# 1-Schematic_ACS2STM-alternate-IDC.net
KiCad netlist of a schematic drawn in EasyEDA
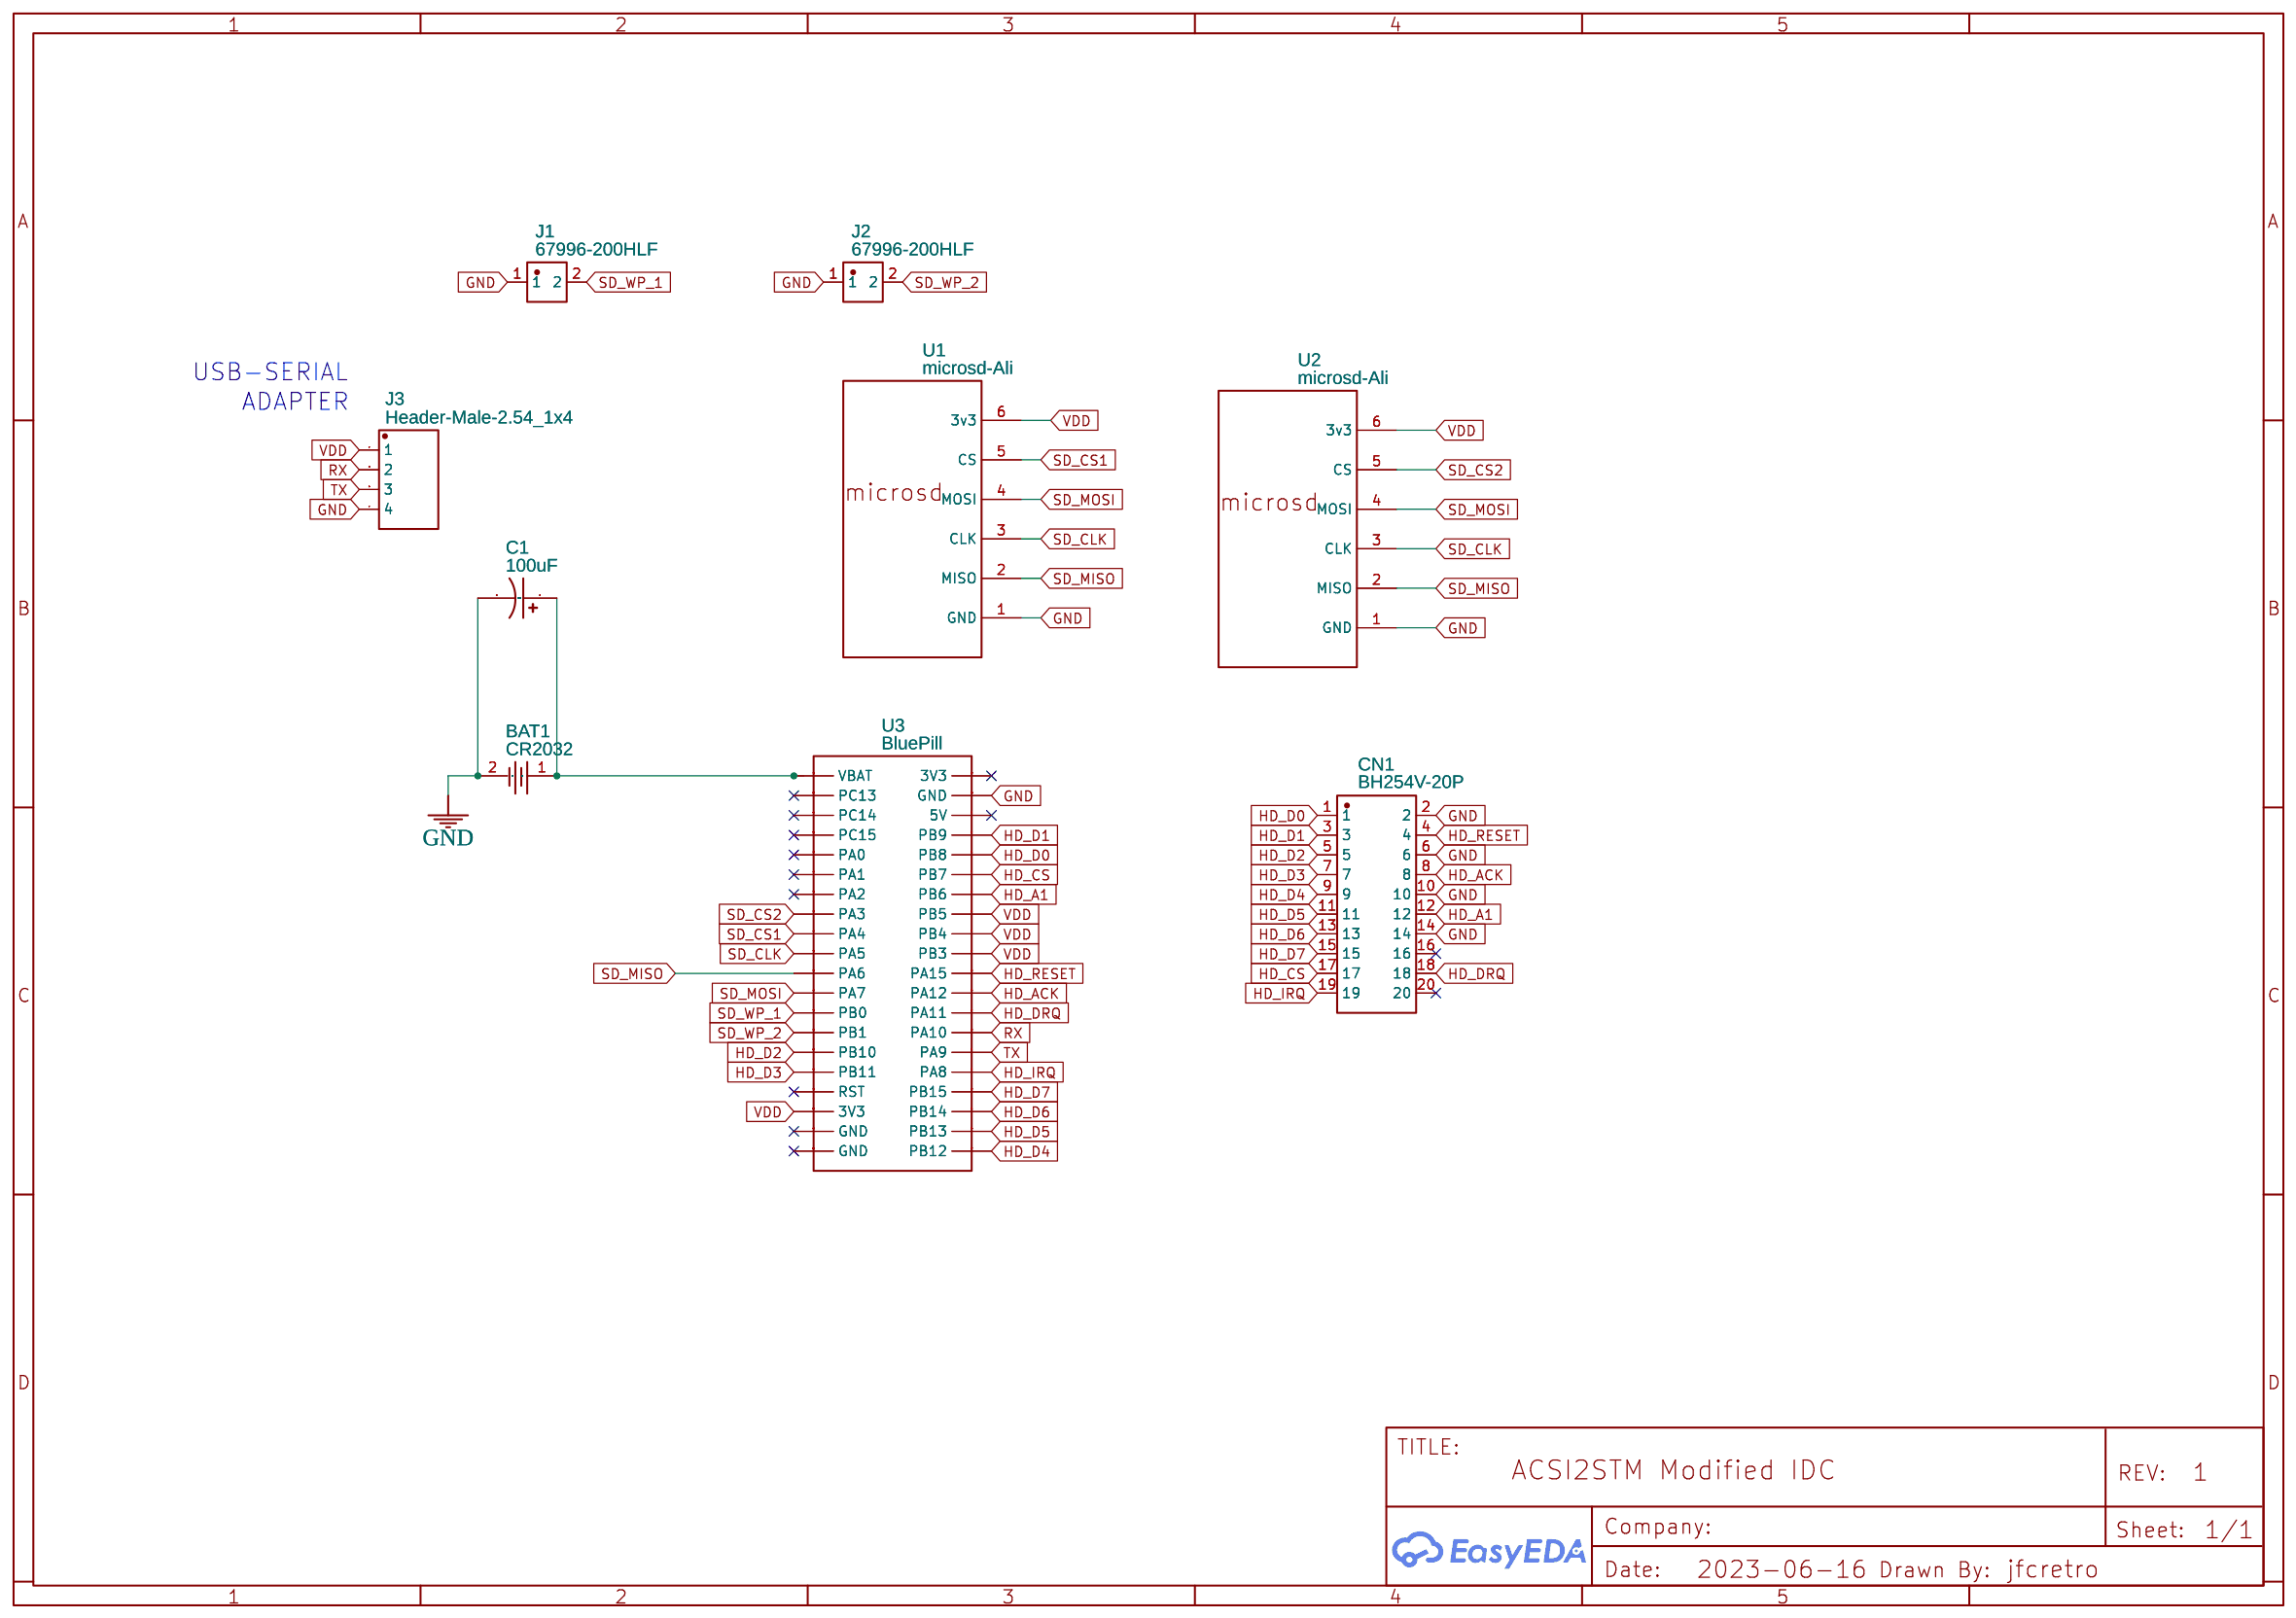
[diagram p0: schematic sheet]

(export (version "E")
  (design (tool "Eeschema 10.0.6"))
  (components
    (comp (ref "BAT1")
      (value "CR2032")
      (fields (field (name "BOM_Supplier Part") "C9900007674"))
      (libsource (lib "") (part "CR2032_C9900007674"))
    )
    (comp (ref "C1") (value "100uF") (libsource (lib "") (part "CE_TH_D6.3×F2.5_US")))
    (comp (ref "CN1")
      (value "BH254V-20P")
      (fields (field (name "BOM_Supplier Part") "C492444"))
      (libsource (lib "") (part "BH254V-20P"))
    )
    (comp (ref "J1")
      (value "67996-200HLF")
      (fields (field (name "BOM_Supplier Part") "C236045"))
      (libsource (lib "") (part "67996-200HLF"))
    )
    (comp (ref "J2")
      (value "67996-200HLF")
      (fields (field (name "BOM_Supplier Part") "C236045"))
      (libsource (lib "") (part "67996-200HLF"))
    )
    (comp (ref "J3")
      (value "Header-Male-2.54_1x4")
      (fields
        (field (name "BOM_Manufacturer Part") "B-2100S04P-A110")
        (field (name "BOM_Supplier Part") "C124378")
      )
      (libsource (lib "") (part "Header-Male-2.54_1x4"))
    )
    (comp (ref "U1") (value "microsd-Ali") (libsource (lib "") (part "microsd-Ali")))
    (comp (ref "U2") (value "microsd-Ali") (libsource (lib "") (part "microsd-Ali")))
    (comp (ref "U3") (value "BluePill") (libsource (lib "") (part "BluePill")))
  )
  (nets
    (net (code "1") (name "GND") (class "Default")
      (node (ref "BAT1") (pin "2") (pinfunction "2_2") (pintype "input"))
      (node (ref "C1") (pin "2") (pinfunction "2_2") (pintype "unspecified"))
      (node (ref "CN1") (pin "10") (pinfunction "10_10") (pintype "unspecified"))
      (node (ref "CN1") (pin "14") (pinfunction "14_14") (pintype "unspecified"))
      (node (ref "CN1") (pin "2") (pinfunction "2_2") (pintype "unspecified"))
      (node (ref "CN1") (pin "6") (pinfunction "6_6") (pintype "unspecified"))
      (node (ref "J1") (pin "1") (pinfunction "1_1") (pintype "unspecified"))
      (node (ref "J2") (pin "1") (pinfunction "1_1") (pintype "unspecified"))
      (node (ref "J3") (pin "4") (pinfunction "4_4") (pintype "unspecified"))
      (node (ref "U1") (pin "1") (pinfunction "GND_1") (pintype "unspecified"))
      (node (ref "U2") (pin "1") (pinfunction "GND_1") (pintype "unspecified"))
      (node (ref "U3") (pin "GND_3") (pinfunction "GND_GND_3") (pintype "unspecified"))
    )
    (net (code "2") (name "HD_A1") (class "Default")
      (node (ref "CN1") (pin "12") (pinfunction "12_12") (pintype "unspecified"))
      (node (ref "U3") (pin "PB6") (pinfunction "PB6_PB6") (pintype "unspecified"))
    )
    (net (code "3") (name "HD_ACK") (class "Default")
      (node (ref "CN1") (pin "8") (pinfunction "8_8") (pintype "unspecified"))
      (node (ref "U3") (pin "PA12") (pinfunction "PA12_PA12") (pintype "unspecified"))
    )
    (net (code "4") (name "HD_CS") (class "Default")
      (node (ref "CN1") (pin "17") (pinfunction "17_17") (pintype "unspecified"))
      (node (ref "U3") (pin "PB7") (pinfunction "PB7_PB7") (pintype "unspecified"))
    )
    (net (code "5") (name "HD_D0") (class "Default")
      (node (ref "CN1") (pin "1") (pinfunction "1_1") (pintype "unspecified"))
      (node (ref "U3") (pin "PB8") (pinfunction "PB8_PB8") (pintype "unspecified"))
    )
    (net (code "6") (name "HD_D1") (class "Default")
      (node (ref "CN1") (pin "3") (pinfunction "3_3") (pintype "unspecified"))
      (node (ref "U3") (pin "PB9") (pinfunction "PB9_PB9") (pintype "unspecified"))
    )
    (net (code "7") (name "HD_D2") (class "Default")
      (node (ref "CN1") (pin "5") (pinfunction "5_5") (pintype "unspecified"))
      (node (ref "U3") (pin "PB10") (pinfunction "PB10_PB10") (pintype "unspecified"))
    )
    (net (code "8") (name "HD_D3") (class "Default")
      (node (ref "CN1") (pin "7") (pinfunction "7_7") (pintype "unspecified"))
      (node (ref "U3") (pin "PB11") (pinfunction "PB11_PB11") (pintype "unspecified"))
    )
    (net (code "9") (name "HD_D4") (class "Default")
      (node (ref "CN1") (pin "9") (pinfunction "9_9") (pintype "unspecified"))
      (node (ref "U3") (pin "PB12") (pinfunction "PB12_PB12") (pintype "unspecified"))
    )
    (net (code "10") (name "HD_D5") (class "Default")
      (node (ref "CN1") (pin "11") (pinfunction "11_11") (pintype "unspecified"))
      (node (ref "U3") (pin "PB13") (pinfunction "PB13_PB13") (pintype "unspecified"))
    )
    (net (code "11") (name "HD_D6") (class "Default")
      (node (ref "CN1") (pin "13") (pinfunction "13_13") (pintype "unspecified"))
      (node (ref "U3") (pin "PB14") (pinfunction "PB14_PB14") (pintype "unspecified"))
    )
    (net (code "12") (name "HD_D7") (class "Default")
      (node (ref "CN1") (pin "15") (pinfunction "15_15") (pintype "unspecified"))
      (node (ref "U3") (pin "PB15") (pinfunction "PB15_PB15") (pintype "unspecified"))
    )
    (net (code "13") (name "HD_DRQ") (class "Default")
      (node (ref "CN1") (pin "18") (pinfunction "18_18") (pintype "unspecified"))
      (node (ref "U3") (pin "PA11") (pinfunction "PA11_PA11") (pintype "unspecified"))
    )
    (net (code "14") (name "HD_IRQ") (class "Default")
      (node (ref "CN1") (pin "19") (pinfunction "19_19") (pintype "unspecified"))
      (node (ref "U3") (pin "PA8") (pinfunction "PA8_PA8") (pintype "unspecified"))
    )
    (net (code "15") (name "HD_RESET") (class "Default")
      (node (ref "CN1") (pin "4") (pinfunction "4_4") (pintype "unspecified"))
      (node (ref "U3") (pin "PA15") (pinfunction "PA15_PA15") (pintype "unspecified"))
    )
    (net (code "16") (name "Net-(BAT1-Pad1)") (class "Default")
      (node (ref "BAT1") (pin "1") (pinfunction "1_1") (pintype "input"))
      (node (ref "C1") (pin "1") (pinfunction "1_1") (pintype "unspecified"))
      (node (ref "U3") (pin "VBAT") (pinfunction "VBAT_VBAT") (pintype "unspecified"))
    )
    (net (code "17") (name "RX") (class "Default")
      (node (ref "J3") (pin "2") (pinfunction "2_2") (pintype "unspecified"))
      (node (ref "U3") (pin "PA10") (pinfunction "PA10_PA10") (pintype "unspecified"))
    )
    (net (code "18") (name "SD_CLK") (class "Default")
      (node (ref "U1") (pin "3") (pinfunction "CLK_3") (pintype "unspecified"))
      (node (ref "U2") (pin "3") (pinfunction "CLK_3") (pintype "unspecified"))
      (node (ref "U3") (pin "PA5") (pinfunction "PA5_PA5") (pintype "unspecified"))
    )
    (net (code "19") (name "SD_CS1") (class "Default")
      (node (ref "U1") (pin "5") (pinfunction "CS_5") (pintype "unspecified"))
      (node (ref "U3") (pin "PA4") (pinfunction "PA4_PA4") (pintype "unspecified"))
    )
    (net (code "20") (name "SD_CS2") (class "Default")
      (node (ref "U2") (pin "5") (pinfunction "CS_5") (pintype "unspecified"))
      (node (ref "U3") (pin "PA3") (pinfunction "PA3_PA3") (pintype "unspecified"))
    )
    (net (code "21") (name "SD_MISO") (class "Default")
      (node (ref "U1") (pin "2") (pinfunction "MISO_2") (pintype "unspecified"))
      (node (ref "U2") (pin "2") (pinfunction "MISO_2") (pintype "unspecified"))
      (node (ref "U3") (pin "PA6") (pinfunction "PA6_PA6") (pintype "unspecified"))
    )
    (net (code "22") (name "SD_MOSI") (class "Default")
      (node (ref "U1") (pin "4") (pinfunction "MOSI_4") (pintype "unspecified"))
      (node (ref "U2") (pin "4") (pinfunction "MOSI_4") (pintype "unspecified"))
      (node (ref "U3") (pin "PA7") (pinfunction "PA7_PA7") (pintype "unspecified"))
    )
    (net (code "23") (name "SD_WP_1") (class "Default")
      (node (ref "J1") (pin "2") (pinfunction "2_2") (pintype "unspecified"))
      (node (ref "U3") (pin "PB0") (pinfunction "PB0_PB0") (pintype "unspecified"))
    )
    (net (code "24") (name "SD_WP_2") (class "Default")
      (node (ref "J2") (pin "2") (pinfunction "2_2") (pintype "unspecified"))
      (node (ref "U3") (pin "PB1") (pinfunction "PB1_PB1") (pintype "unspecified"))
    )
    (net (code "25") (name "TX") (class "Default")
      (node (ref "J3") (pin "3") (pinfunction "3_3") (pintype "unspecified"))
      (node (ref "U3") (pin "PA9") (pinfunction "PA9_PA9") (pintype "unspecified"))
    )
    (net (code "26") (name "VDD") (class "Default")
      (node (ref "J3") (pin "1") (pinfunction "1_1") (pintype "unspecified"))
      (node (ref "U1") (pin "6") (pinfunction "3v3_6") (pintype "unspecified"))
      (node (ref "U2") (pin "6") (pinfunction "3v3_6") (pintype "unspecified"))
      (node (ref "U3") (pin "3V3_1") (pinfunction "3V3_3V3_1") (pintype "unspecified"))
      (node (ref "U3") (pin "PB3") (pinfunction "PB3_PB3") (pintype "unspecified"))
      (node (ref "U3") (pin "PB4") (pinfunction "PB4_PB4") (pintype "unspecified"))
      (node (ref "U3") (pin "PB5") (pinfunction "PB5_PB5") (pintype "unspecified"))
    )
    (net (code "27") (name "unconnected-(CN1-Pad16)") (class "Default")
      (node (ref "CN1") (pin "16") (pinfunction "16_16") (pintype "unspecified+no_connect"))
    )
    (net (code "28") (name "unconnected-(CN1-Pad20)") (class "Default")
      (node (ref "CN1") (pin "20") (pinfunction "20_20") (pintype "unspecified+no_connect"))
    )
    (net (code "29") (name "unconnected-(U3-3V3-Pad3V3_2)") (class "Default")
      (node (ref "U3") (pin "3V3_2") (pinfunction "3V3_3V3_2") (pintype "unspecified+no_connect"))
    )
    (net (code "30") (name "unconnected-(U3-GND-PadGND_1)") (class "Default")
      (node (ref "U3") (pin "GND_1") (pinfunction "GND_GND_1") (pintype "unspecified+no_connect"))
    )
    (net (code "31") (name "unconnected-(U3-GND-PadGND_2)") (class "Default")
      (node (ref "U3") (pin "GND_2") (pinfunction "GND_GND_2") (pintype "unspecified+no_connect"))
    )
    (net (code "32") (name "unconnected-(U3-Pad5V)") (class "Default")
      (node (ref "U3") (pin "5V") (pinfunction "5V_5V") (pintype "unspecified+no_connect"))
    )
    (net (code "33") (name "unconnected-(U3-PadPA0)") (class "Default")
      (node (ref "U3") (pin "PA0") (pinfunction "PA0_PA0") (pintype "unspecified+no_connect"))
    )
    (net (code "34") (name "unconnected-(U3-PadPA1)") (class "Default")
      (node (ref "U3") (pin "PA1") (pinfunction "PA1_PA1") (pintype "unspecified+no_connect"))
    )
    (net (code "35") (name "unconnected-(U3-PadPA2)") (class "Default")
      (node (ref "U3") (pin "PA2") (pinfunction "PA2_PA2") (pintype "unspecified+no_connect"))
    )
    (net (code "36") (name "unconnected-(U3-PadPC13)") (class "Default")
      (node (ref "U3") (pin "PC13") (pinfunction "PC13_PC13") (pintype "unspecified+no_connect"))
    )
    (net (code "37") (name "unconnected-(U3-PadPC14)") (class "Default")
      (node (ref "U3") (pin "PC14") (pinfunction "PC14_PC14") (pintype "unspecified+no_connect"))
    )
    (net (code "38") (name "unconnected-(U3-PadPC15)") (class "Default")
      (node (ref "U3") (pin "PC15") (pinfunction "PC15_PC15") (pintype "unspecified+no_connect"))
    )
    (net (code "39") (name "unconnected-(U3-PadRST)") (class "Default")
      (node (ref "U3") (pin "RST") (pinfunction "RST_RST") (pintype "unspecified+no_connect"))
    )
  )
)
